# main.net
KiCad netlist of a schematic drawn in Altium Designer
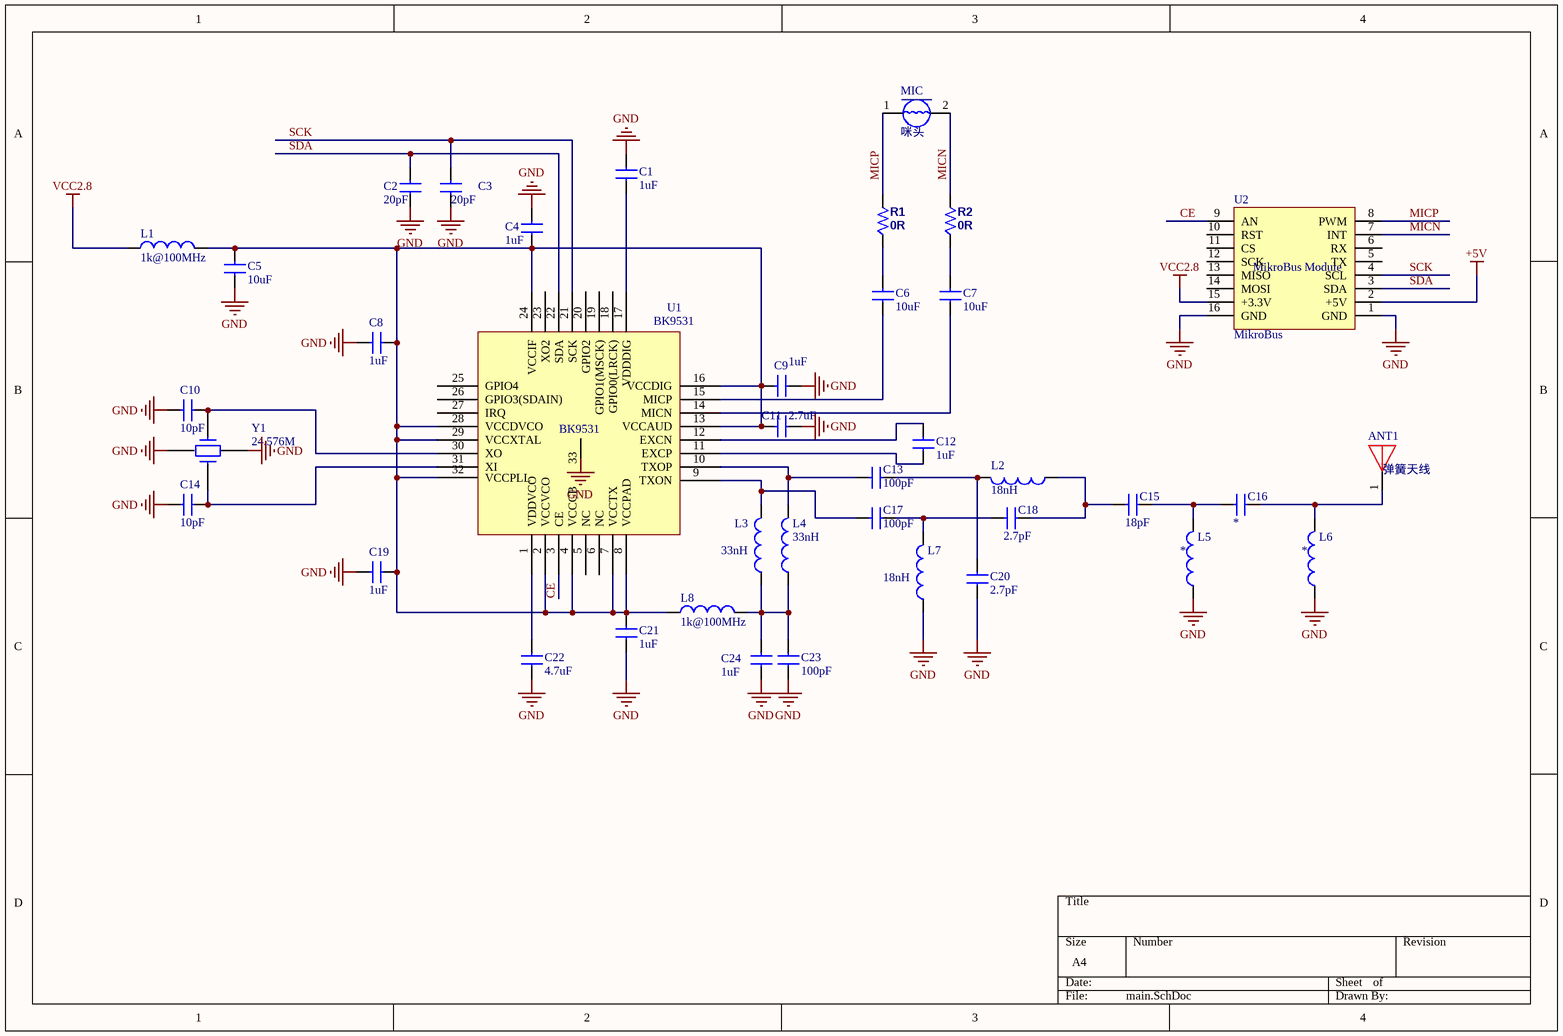
[diagram p0: main.SchDoc]

(export (version "E")
  (design (tool "Eeschema 10.0.6"))
  (components
    (comp (ref "ANT1")
      (value "弹簧天线")
      (footprint "ANT")
      (description "ANT")
      (libsource (lib "二极管") (part "ANT"))
    )
    (comp (ref "C1")
      (value "1uF")
      (footprint "C0603")
      (description "0603-10pF/50V 贴片层叠电容")
      (libsource (lib "兰格封装") (part "CAP 0603-10pF/50V"))
    )
    (comp (ref "C2")
      (value "20pF")
      (footprint "C0603")
      (description "0603-10pF/50V 贴片层叠电容")
      (libsource (lib "兰格封装") (part "CAP 0603-10pF/50V"))
    )
    (comp (ref "C3")
      (value "20pF")
      (footprint "C0603")
      (description "0603-10pF/50V 贴片层叠电容")
      (libsource (lib "兰格封装") (part "CAP 0603-10pF/50V"))
    )
    (comp (ref "C4")
      (value "1uF")
      (footprint "C0603")
      (description "0603-10pF/50V 贴片层叠电容")
      (libsource (lib "兰格封装") (part "CAP 0603-10pF/50V"))
    )
    (comp (ref "C5")
      (value "10uF")
      (footprint "C0603")
      (description "0603-10pF/50V 贴片层叠电容")
      (libsource (lib "兰格封装") (part "CAP 0603-10pF/50V"))
    )
    (comp (ref "C6")
      (value "10uF")
      (footprint "C0603")
      (description "0603-10pF/50V 贴片层叠电容")
      (libsource (lib "兰格封装") (part "CAP 0603-10pF/50V"))
    )
    (comp (ref "C7")
      (value "10uF")
      (footprint "C0603")
      (description "0603-10pF/50V 贴片层叠电容")
      (libsource (lib "兰格封装") (part "CAP 0603-10pF/50V"))
    )
    (comp (ref "C8")
      (value "1uF")
      (footprint "C0603")
      (description "0603-10pF/50V 贴片层叠电容")
      (libsource (lib "兰格封装") (part "CAP 0603-10pF/50V"))
    )
    (comp (ref "C9")
      (value "1uF")
      (footprint "C0603")
      (description "0603-10pF/50V 贴片层叠电容")
      (libsource (lib "兰格封装") (part "CAP 0603-10pF/50V"))
    )
    (comp (ref "C10")
      (value "10pF")
      (footprint "C0603")
      (description "0603-10pF/50V 贴片层叠电容")
      (libsource (lib "兰格封装") (part "CAP 0603-10pF/50V"))
    )
    (comp (ref "C11")
      (value "2.7uF")
      (footprint "C0603")
      (description "0603-10pF/50V 贴片层叠电容")
      (libsource (lib "兰格封装") (part "CAP 0603-10pF/50V"))
    )
    (comp (ref "C12")
      (value "1uF")
      (footprint "C0603")
      (description "0603-10pF/50V 贴片层叠电容")
      (libsource (lib "兰格封装") (part "CAP 0603-10pF/50V"))
    )
    (comp (ref "C13")
      (value "100pF")
      (footprint "C0603")
      (description "0603-10pF/50V 贴片层叠电容")
      (libsource (lib "兰格封装") (part "CAP 0603-10pF/50V"))
    )
    (comp (ref "C14")
      (value "10pF")
      (footprint "C0603")
      (description "0603-10pF/50V 贴片层叠电容")
      (libsource (lib "兰格封装") (part "CAP 0603-10pF/50V"))
    )
    (comp (ref "C15")
      (value "18pF")
      (footprint "C0603")
      (description "0603-10pF/50V 贴片层叠电容")
      (libsource (lib "兰格封装") (part "CAP 0603-10pF/50V"))
    )
    (comp (ref "C16")
      (value "*")
      (footprint "C0603")
      (description "0603-10pF/50V 贴片层叠电容")
      (libsource (lib "兰格封装") (part "CAP 0603-10pF/50V"))
    )
    (comp (ref "C17")
      (value "100pF")
      (footprint "C0603")
      (description "0603-10pF/50V 贴片层叠电容")
      (libsource (lib "兰格封装") (part "CAP 0603-10pF/50V"))
    )
    (comp (ref "C18")
      (value "2.7pF")
      (footprint "C0603")
      (description "0603-10pF/50V 贴片层叠电容")
      (libsource (lib "兰格封装") (part "CAP 0603-10pF/50V"))
    )
    (comp (ref "C19")
      (value "1uF")
      (footprint "C0603")
      (description "0603-10pF/50V 贴片层叠电容")
      (libsource (lib "兰格封装") (part "CAP 0603-10pF/50V"))
    )
    (comp (ref "C20")
      (value "2.7pF")
      (footprint "C0603")
      (description "0603-10pF/50V 贴片层叠电容")
      (libsource (lib "兰格封装") (part "CAP 0603-10pF/50V"))
    )
    (comp (ref "C21")
      (value "1uF")
      (footprint "C0603")
      (description "0603-10pF/50V 贴片层叠电容")
      (libsource (lib "兰格封装") (part "CAP 0603-10pF/50V"))
    )
    (comp (ref "C22")
      (value "4.7uF")
      (footprint "C0603")
      (description "0603-10pF/50V 贴片层叠电容")
      (libsource (lib "兰格封装") (part "CAP 0603-10pF/50V"))
    )
    (comp (ref "C23")
      (value "100pF")
      (footprint "C0603")
      (description "0603-10pF/50V 贴片层叠电容")
      (libsource (lib "兰格封装") (part "CAP 0603-10pF/50V"))
    )
    (comp (ref "C24")
      (value "1uF")
      (footprint "C0603")
      (description "0603-10pF/50V 贴片层叠电容")
      (libsource (lib "兰格封装") (part "CAP 0603-10pF/50V"))
    )
    (comp (ref "L1")
      (value "1k@100MHz")
      (footprint "L0603")
      (description "磁珠")
      (libsource (lib "兰格封装") (part "电感  贴片  33UH"))
    )
    (comp (ref "L2")
      (value "18nH")
      (footprint "L0603")
      (description "磁珠")
      (libsource (lib "兰格封装") (part "电感  贴片  33UH"))
    )
    (comp (ref "L3")
      (value "33nH")
      (footprint "L0603")
      (description "磁珠")
      (libsource (lib "兰格封装") (part "电感  贴片  33UH"))
    )
    (comp (ref "L4")
      (value "33nH")
      (footprint "L0603")
      (description "磁珠")
      (libsource (lib "兰格封装") (part "电感  贴片  33UH"))
    )
    (comp (ref "L5")
      (value "*")
      (footprint "L0603")
      (description "磁珠")
      (libsource (lib "兰格封装") (part "电感  贴片  33UH"))
    )
    (comp (ref "L6")
      (value "*")
      (footprint "L0603")
      (description "磁珠")
      (libsource (lib "兰格封装") (part "电感  贴片  33UH"))
    )
    (comp (ref "L7")
      (value "18nH")
      (footprint "L0603")
      (description "磁珠")
      (libsource (lib "兰格封装") (part "电感  贴片  33UH"))
    )
    (comp (ref "L8")
      (value "1k@100MHz")
      (footprint "L0603")
      (description "磁珠")
      (libsource (lib "兰格封装") (part "电感  贴片  33UH"))
    )
    (comp (ref "MIC") (value "咪头") (footprint "MIC") (libsource (lib "二极管") (part "MIC")))
    (comp (ref "R1")
      (value "0R")
      (footprint "R0603")
      (description "1206  K  5%  HS  贴片电阻")
      (libsource (lib "兰格封装") (part "RES1"))
    )
    (comp (ref "R2")
      (value "0R")
      (footprint "R0603")
      (description "1206  K  5%  HS  贴片电阻")
      (libsource (lib "兰格封装") (part "RES1"))
    )
    (comp (ref "U1")
      (value "BK9531")
      (footprint "QFN32")
      (description "QFN5x5 32")
      (libsource (lib "集成IC") (part "BK9531"))
    )
    (comp (ref "U2") (value "MikroBus") (footprint "MikroBus") (libsource (lib "集成IC") (part "MikroBus")))
    (comp (ref "Y1")
      (value "24.576M")
      (footprint "晶振   有源2520")
      (description "（未入库）24.576MHz  2520")
      (libsource (lib "晶体") (part "晶振  24.576MHz  49SMD"))
    )
  )
  (nets
    (net (code "1") (name "+5V") (class "Default")
      (node (ref "U2") (pin "2") (pinfunction "+5V_2") (pintype "passive"))
    )
    (net (code "2") (name "/CE") (class "Default")
      (node (ref "U1") (pin "3") (pinfunction "CE_3") (pintype "passive"))
      (node (ref "U2") (pin "9") (pinfunction "AN_9") (pintype "passive"))
    )
    (net (code "3") (name "/MICN") (class "Default")
      (node (ref "MIC") (pin "2") (pinfunction "2_2") (pintype "passive"))
      (node (ref "R2") (pin "2") (pintype "passive"))
      (node (ref "U2") (pin "7") (pinfunction "INT_7") (pintype "passive"))
    )
    (net (code "4") (name "/MICP") (class "Default")
      (node (ref "MIC") (pin "1") (pinfunction "1_1") (pintype "passive"))
      (node (ref "R1") (pin "2") (pintype "passive"))
      (node (ref "U2") (pin "8") (pinfunction "PWM_8") (pintype "passive"))
    )
    (net (code "5") (name "/SCK") (class "Default")
      (node (ref "C3") (pin "2") (pinfunction "2_2") (pintype "passive"))
      (node (ref "U1") (pin "21") (pinfunction "SCK_21") (pintype "passive"))
      (node (ref "U2") (pin "4") (pinfunction "SCL_4") (pintype "passive"))
    )
    (net (code "6") (name "/SDA") (class "Default")
      (node (ref "C2") (pin "2") (pinfunction "2_2") (pintype "passive"))
      (node (ref "U1") (pin "22") (pinfunction "SDA_22") (pintype "passive"))
      (node (ref "U2") (pin "3") (pinfunction "SDA_3") (pintype "passive"))
    )
    (net (code "7") (name "GND") (class "Default")
      (node (ref "C1") (pin "2") (pinfunction "2_2") (pintype "passive"))
      (node (ref "C10") (pin "2") (pinfunction "2_2") (pintype "passive"))
      (node (ref "C11") (pin "1") (pinfunction "1_1") (pintype "passive"))
      (node (ref "C14") (pin "2") (pinfunction "2_2") (pintype "passive"))
      (node (ref "C19") (pin "1") (pinfunction "1_1") (pintype "passive"))
      (node (ref "C2") (pin "1") (pinfunction "1_1") (pintype "passive"))
      (node (ref "C20") (pin "1") (pinfunction "1_1") (pintype "passive"))
      (node (ref "C21") (pin "2") (pinfunction "2_2") (pintype "passive"))
      (node (ref "C22") (pin "2") (pinfunction "2_2") (pintype "passive"))
      (node (ref "C23") (pin "2") (pinfunction "2_2") (pintype "passive"))
      (node (ref "C24") (pin "2") (pinfunction "2_2") (pintype "passive"))
      (node (ref "C3") (pin "1") (pinfunction "1_1") (pintype "passive"))
      (node (ref "C4") (pin "2") (pinfunction "2_2") (pintype "passive"))
      (node (ref "C5") (pin "1") (pinfunction "1_1") (pintype "passive"))
      (node (ref "C8") (pin "1") (pinfunction "1_1") (pintype "passive"))
      (node (ref "C9") (pin "1") (pinfunction "1_1") (pintype "passive"))
      (node (ref "L5") (pin "1") (pinfunction "1_1") (pintype "passive"))
      (node (ref "L6") (pin "1") (pinfunction "1_1") (pintype "passive"))
      (node (ref "L7") (pin "1") (pinfunction "1_1") (pintype "passive"))
      (node (ref "U1") (pin "33") (pintype "passive"))
      (node (ref "U2") (pin "1") (pinfunction "GND_1") (pintype "passive"))
      (node (ref "U2") (pin "16") (pinfunction "GND_16") (pintype "passive"))
      (node (ref "Y1") (pin "2") (pinfunction "2_2") (pintype "passive"))
      (node (ref "Y1") (pin "4") (pinfunction "4_4") (pintype "passive"))
    )
    (net (code "8") (name "Net-(ANT1-Pad1)") (class "Default")
      (node (ref "ANT1") (pin "1") (pinfunction "1_1") (pintype "passive"))
      (node (ref "C16") (pin "1") (pinfunction "1_1") (pintype "passive"))
      (node (ref "L6") (pin "2") (pinfunction "2_2") (pintype "passive"))
    )
    (net (code "9") (name "Net-(C6-Pad1)") (class "Default")
      (node (ref "C6") (pin "1") (pinfunction "1_1") (pintype "passive"))
      (node (ref "R1") (pin "1") (pintype "passive"))
    )
    (net (code "10") (name "Net-(C7-Pad1)") (class "Default")
      (node (ref "C7") (pin "1") (pinfunction "1_1") (pintype "passive"))
      (node (ref "R2") (pin "1") (pintype "passive"))
    )
    (net (code "11") (name "Net-(C13-Pad2)") (class "Default")
      (node (ref "C13") (pin "2") (pinfunction "2_2") (pintype "passive"))
      (node (ref "C20") (pin "2") (pinfunction "2_2") (pintype "passive"))
      (node (ref "L2") (pin "2") (pinfunction "2_2") (pintype "passive"))
    )
    (net (code "12") (name "Net-(C15-Pad1)") (class "Default")
      (node (ref "C15") (pin "1") (pinfunction "1_1") (pintype "passive"))
      (node (ref "C16") (pin "2") (pinfunction "2_2") (pintype "passive"))
      (node (ref "L5") (pin "2") (pinfunction "2_2") (pintype "passive"))
    )
    (net (code "13") (name "Net-(C15-Pad2)") (class "Default")
      (node (ref "C15") (pin "2") (pinfunction "2_2") (pintype "passive"))
      (node (ref "C18") (pin "1") (pinfunction "1_1") (pintype "passive"))
      (node (ref "L2") (pin "1") (pinfunction "1_1") (pintype "passive"))
    )
    (net (code "14") (name "Net-(C17-Pad2)") (class "Default")
      (node (ref "C17") (pin "2") (pinfunction "2_2") (pintype "passive"))
      (node (ref "C18") (pin "2") (pinfunction "2_2") (pintype "passive"))
      (node (ref "L7") (pin "2") (pinfunction "2_2") (pintype "passive"))
    )
    (net (code "15") (name "Net-(C23-Pad1)") (class "Default")
      (node (ref "C23") (pin "1") (pinfunction "1_1") (pintype "passive"))
      (node (ref "C24") (pin "1") (pinfunction "1_1") (pintype "passive"))
      (node (ref "L3") (pin "1") (pinfunction "1_1") (pintype "passive"))
      (node (ref "L4") (pin "1") (pinfunction "1_1") (pintype "passive"))
      (node (ref "L8") (pin "2") (pinfunction "2_2") (pintype "passive"))
    )
    (net (code "16") (name "Net-(U1-EXCN)") (class "Default")
      (node (ref "C12") (pin "1") (pinfunction "1_1") (pintype "passive"))
      (node (ref "U1") (pin "12") (pinfunction "EXCN_12") (pintype "passive"))
    )
    (net (code "17") (name "Net-(U1-EXCP)") (class "Default")
      (node (ref "C12") (pin "2") (pinfunction "2_2") (pintype "passive"))
      (node (ref "U1") (pin "11") (pinfunction "EXCP_11") (pintype "passive"))
    )
    (net (code "18") (name "Net-(U1-MICN)") (class "Default")
      (node (ref "C7") (pin "2") (pinfunction "2_2") (pintype "passive"))
      (node (ref "U1") (pin "14") (pinfunction "MICN_14") (pintype "passive"))
    )
    (net (code "19") (name "Net-(U1-MICP)") (class "Default")
      (node (ref "C6") (pin "2") (pinfunction "2_2") (pintype "passive"))
      (node (ref "U1") (pin "15") (pinfunction "MICP_15") (pintype "passive"))
    )
    (net (code "20") (name "Net-(U1-TXON)") (class "Default")
      (node (ref "C17") (pin "1") (pinfunction "1_1") (pintype "passive"))
      (node (ref "L3") (pin "2") (pinfunction "2_2") (pintype "passive"))
      (node (ref "U1") (pin "9") (pinfunction "TXON_9") (pintype "passive"))
    )
    (net (code "21") (name "Net-(U1-TXOP)") (class "Default")
      (node (ref "C13") (pin "1") (pinfunction "1_1") (pintype "passive"))
      (node (ref "L4") (pin "2") (pinfunction "2_2") (pintype "passive"))
      (node (ref "U1") (pin "10") (pinfunction "TXOP_10") (pintype "passive"))
    )
    (net (code "22") (name "Net-(U1-VCCAUD)") (class "Default")
      (node (ref "C11") (pin "2") (pinfunction "2_2") (pintype "passive"))
      (node (ref "C19") (pin "2") (pinfunction "2_2") (pintype "passive"))
      (node (ref "C21") (pin "1") (pinfunction "1_1") (pintype "passive"))
      (node (ref "C4") (pin "1") (pinfunction "1_1") (pintype "passive"))
      (node (ref "C5") (pin "2") (pinfunction "2_2") (pintype "passive"))
      (node (ref "C8") (pin "2") (pinfunction "2_2") (pintype "passive"))
      (node (ref "C9") (pin "2") (pinfunction "2_2") (pintype "passive"))
      (node (ref "L1") (pin "2") (pinfunction "2_2") (pintype "passive"))
      (node (ref "L8") (pin "1") (pinfunction "1_1") (pintype "passive"))
      (node (ref "U1") (pin "13") (pinfunction "VCCAUD_13") (pintype "passive"))
      (node (ref "U1") (pin "16") (pinfunction "VCCDIG_16") (pintype "passive"))
      (node (ref "U1") (pin "2") (pinfunction "VCCVCO_2") (pintype "passive"))
      (node (ref "U1") (pin "24") (pinfunction "VCCIF_24") (pintype "passive"))
      (node (ref "U1") (pin "28") (pinfunction "VCCDVCO_28") (pintype "passive"))
      (node (ref "U1") (pin "29") (pinfunction "VCCXTAL_29") (pintype "passive"))
      (node (ref "U1") (pin "32") (pinfunction "VCCPLL_32") (pintype "passive"))
      (node (ref "U1") (pin "4") (pinfunction "VCCCB_4") (pintype "passive"))
      (node (ref "U1") (pin "7") (pinfunction "VCCTX_7") (pintype "passive"))
      (node (ref "U1") (pin "8") (pinfunction "VCCPAD_8") (pintype "passive"))
    )
    (net (code "23") (name "Net-(U1-VDDDIG)") (class "Default")
      (node (ref "C1") (pin "1") (pinfunction "1_1") (pintype "passive"))
      (node (ref "U1") (pin "17") (pinfunction "VDDDIG_17") (pintype "passive"))
    )
    (net (code "24") (name "Net-(U1-VDDVCO)") (class "Default")
      (node (ref "C22") (pin "1") (pinfunction "1_1") (pintype "passive"))
      (node (ref "U1") (pin "1") (pinfunction "VDDVCO_1") (pintype "passive"))
    )
    (net (code "25") (name "Net-(U1-XI)") (class "Default")
      (node (ref "C14") (pin "1") (pinfunction "1_1") (pintype "passive"))
      (node (ref "U1") (pin "31") (pinfunction "XI_31") (pintype "passive"))
      (node (ref "Y1") (pin "1") (pinfunction "1_1") (pintype "passive"))
    )
    (net (code "26") (name "Net-(U1-XO)") (class "Default")
      (node (ref "C10") (pin "1") (pinfunction "1_1") (pintype "passive"))
      (node (ref "U1") (pin "30") (pinfunction "XO_30") (pintype "passive"))
      (node (ref "Y1") (pin "3") (pinfunction "3_3") (pintype "passive"))
    )
    (net (code "27") (name "VCC2.8") (class "Default")
      (node (ref "L1") (pin "1") (pinfunction "1_1") (pintype "passive"))
      (node (ref "U2") (pin "15") (pinfunction "+3.3V_15") (pintype "passive"))
    )
    (net (code "28") (name "unconnected-(U1-GPIO0(LRCK)-Pad18)") (class "Default")
      (node (ref "U1") (pin "18") (pinfunction "GPIO0(LRCK)_18") (pintype "passive"))
    )
    (net (code "29") (name "unconnected-(U1-GPIO1(MSCK)-Pad19)") (class "Default")
      (node (ref "U1") (pin "19") (pinfunction "GPIO1(MSCK)_19") (pintype "passive"))
    )
    (net (code "30") (name "unconnected-(U1-GPIO2-Pad20)") (class "Default")
      (node (ref "U1") (pin "20") (pinfunction "GPIO2_20") (pintype "passive"))
    )
    (net (code "31") (name "unconnected-(U1-GPIO3(SDAIN)-Pad26)") (class "Default")
      (node (ref "U1") (pin "26") (pinfunction "GPIO3(SDAIN)_26") (pintype "passive"))
    )
    (net (code "32") (name "unconnected-(U1-GPIO4-Pad25)") (class "Default")
      (node (ref "U1") (pin "25") (pinfunction "GPIO4_25") (pintype "passive"))
    )
    (net (code "33") (name "unconnected-(U1-IRQ-Pad27)") (class "Default")
      (node (ref "U1") (pin "27") (pinfunction "IRQ_27") (pintype "passive"))
    )
    (net (code "34") (name "unconnected-(U1-NC-Pad5)") (class "Default")
      (node (ref "U1") (pin "5") (pinfunction "NC_5") (pintype "passive"))
    )
    (net (code "35") (name "unconnected-(U1-NC-Pad6)") (class "Default")
      (node (ref "U1") (pin "6") (pinfunction "NC_6") (pintype "passive"))
    )
    (net (code "36") (name "unconnected-(U1-XO2-Pad23)") (class "Default")
      (node (ref "U1") (pin "23") (pinfunction "XO2_23") (pintype "passive"))
    )
    (net (code "37") (name "unconnected-(U2-CS-Pad11)") (class "Default")
      (node (ref "U2") (pin "11") (pinfunction "CS_11") (pintype "passive"))
    )
    (net (code "38") (name "unconnected-(U2-MISO-Pad13)") (class "Default")
      (node (ref "U2") (pin "13") (pinfunction "MISO_13") (pintype "passive"))
    )
    (net (code "39") (name "unconnected-(U2-MOSI-Pad14)") (class "Default")
      (node (ref "U2") (pin "14") (pinfunction "MOSI_14") (pintype "passive"))
    )
    (net (code "40") (name "unconnected-(U2-RST-Pad10)") (class "Default")
      (node (ref "U2") (pin "10") (pinfunction "RST_10") (pintype "passive"))
    )
    (net (code "41") (name "unconnected-(U2-RX-Pad6)") (class "Default")
      (node (ref "U2") (pin "6") (pinfunction "RX_6") (pintype "passive"))
    )
    (net (code "42") (name "unconnected-(U2-SCK-Pad12)") (class "Default")
      (node (ref "U2") (pin "12") (pinfunction "SCK_12") (pintype "passive"))
    )
    (net (code "43") (name "unconnected-(U2-TX-Pad5)") (class "Default")
      (node (ref "U2") (pin "5") (pinfunction "TX_5") (pintype "passive"))
    )
  )
)
